# PHOTODIODE.net
KiCad netlist of a schematic drawn in Altium Designer
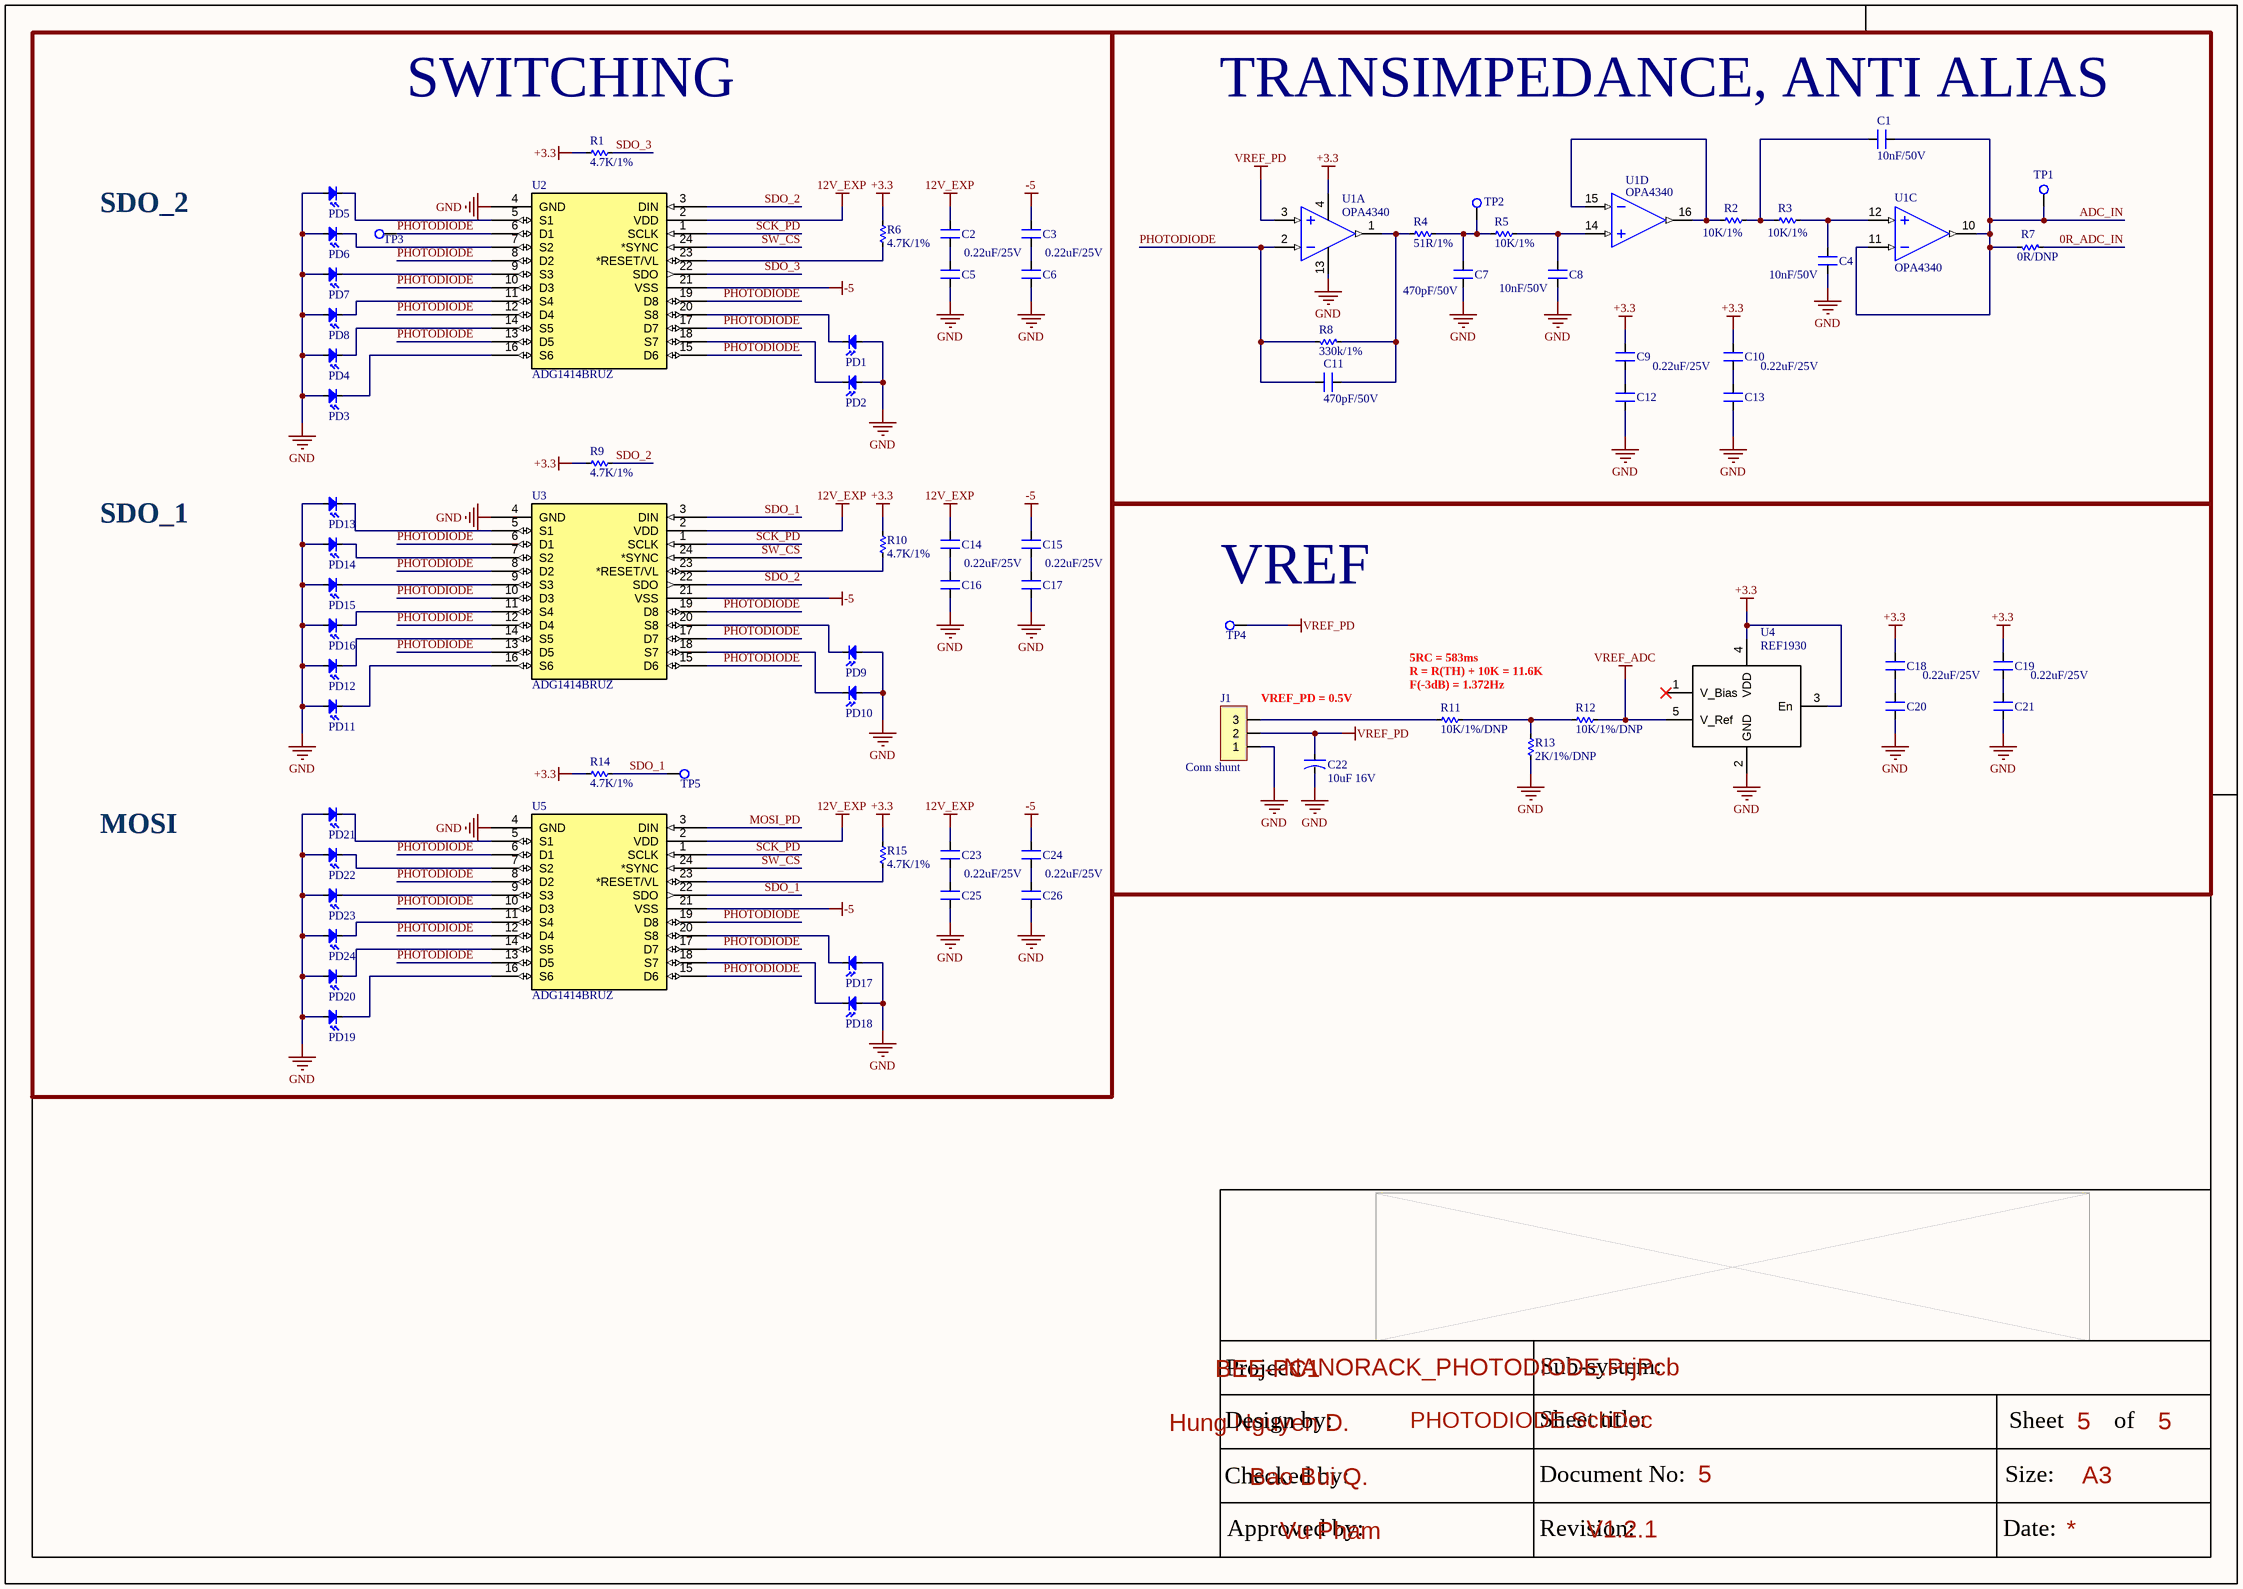
[diagram p0: PHOTODIODE.SchDoc]

(export (version "E")
  (design (tool "Eeschema 10.0.6"))
  (components
    (comp (ref "C1")
      (value "10nF/50V")
      (footprint "CN-SMD-0603")
      (description "CL10B103KB8NNNC")
      (libsource (lib "Capacitors") (part "CM"))
    )
    (comp (ref "C2")
      (value "0.22uF/25V")
      (footprint "CN-SMD-0603")
      (description "CL10B224KA8NNNC")
      (libsource (lib "Capacitors") (part "CM"))
    )
    (comp (ref "C3")
      (value "0.22uF/25V")
      (footprint "CN-SMD-0603")
      (description "CL10B224KA8NNNC")
      (libsource (lib "Capacitors") (part "CM"))
    )
    (comp (ref "C4")
      (value "10nF/50V")
      (footprint "CN-SMD-0603")
      (description "CL10B103KB8NNNC")
      (libsource (lib "Capacitors") (part "CM"))
    )
    (comp (ref "C5")
      (value "0.22uF/25V")
      (footprint "CN-SMD-0603")
      (description "CL10B224KA8NNNC")
      (libsource (lib "Capacitors") (part "CM"))
    )
    (comp (ref "C6")
      (value "0.22uF/25V")
      (footprint "CN-SMD-0603")
      (description "CL10B224KA8NNNC")
      (libsource (lib "Capacitors") (part "CM"))
    )
    (comp (ref "C7")
      (value "470pF/50V")
      (footprint "CN-SMD-0603")
      (description "CL10B471KB8NNNC")
      (libsource (lib "Capacitors") (part "CM"))
    )
    (comp (ref "C8")
      (value "10nF/50V")
      (footprint "CN-SMD-0603")
      (description "CL10B103KB8NNNC")
      (libsource (lib "Capacitors") (part "CM"))
    )
    (comp (ref "C9")
      (value "0.22uF/25V")
      (footprint "CN-SMD-0603")
      (description "CL10B224KA8NNNC")
      (libsource (lib "Capacitors") (part "CM"))
    )
    (comp (ref "C10")
      (value "0.22uF/25V")
      (footprint "CN-SMD-0603")
      (description "CL10B224KA8NNNC")
      (libsource (lib "Capacitors") (part "CM"))
    )
    (comp (ref "C11")
      (value "470pF/50V")
      (footprint "CN-SMD-0603")
      (description "CL10B471KB8NNNC")
      (libsource (lib "Capacitors") (part "CM"))
    )
    (comp (ref "C12")
      (value "0.22uF/25V")
      (footprint "CN-SMD-0603")
      (description "CL10B224KA8NNNC")
      (libsource (lib "Capacitors") (part "CM"))
    )
    (comp (ref "C13")
      (value "0.22uF/25V")
      (footprint "CN-SMD-0603")
      (description "CL10B224KA8NNNC")
      (libsource (lib "Capacitors") (part "CM"))
    )
    (comp (ref "C14")
      (value "0.22uF/25V")
      (footprint "CN-SMD-0603")
      (description "CL10B224KA8NNNC")
      (libsource (lib "Capacitors") (part "CM"))
    )
    (comp (ref "C15")
      (value "0.22uF/25V")
      (footprint "CN-SMD-0603")
      (description "CL10B224KA8NNNC")
      (libsource (lib "Capacitors") (part "CM"))
    )
    (comp (ref "C16")
      (value "0.22uF/25V")
      (footprint "CN-SMD-0603")
      (description "CL10B224KA8NNNC")
      (libsource (lib "Capacitors") (part "CM"))
    )
    (comp (ref "C17")
      (value "0.22uF/25V")
      (footprint "CN-SMD-0603")
      (description "CL10B224KA8NNNC")
      (libsource (lib "Capacitors") (part "CM"))
    )
    (comp (ref "C18")
      (value "0.22uF/25V")
      (footprint "CN-SMD-0603")
      (description "CL10B224KA8NNNC")
      (libsource (lib "Capacitors") (part "CM"))
    )
    (comp (ref "C19")
      (value "0.22uF/25V")
      (footprint "CN-SMD-0603")
      (description "CL10B224KA8NNNC")
      (libsource (lib "Capacitors") (part "CM"))
    )
    (comp (ref "C20")
      (value "0.22uF/25V")
      (footprint "CN-SMD-0603")
      (description "CL10B224KA8NNNC")
      (libsource (lib "Capacitors") (part "CM"))
    )
    (comp (ref "C21")
      (value "0.22uF/25V")
      (footprint "CN-SMD-0603")
      (description "CL10B224KA8NNNC")
      (libsource (lib "Capacitors") (part "CM"))
    )
    (comp (ref "C22")
      (value "10uF 16V")
      (footprint "CAP_TANT_1206")
      (description "TAJA106K016RNJ")
      (fields (field (name "PUBLISHER") "Altium Limited"))
      (libsource (lib "Library_HUNG") (part "CN-ALU-SMD"))
    )
    (comp (ref "C23")
      (value "0.22uF/25V")
      (footprint "CN-SMD-0603")
      (description "CL10B224KA8NNNC")
      (libsource (lib "Capacitors") (part "CM"))
    )
    (comp (ref "C24")
      (value "0.22uF/25V")
      (footprint "CN-SMD-0603")
      (description "CL10B224KA8NNNC")
      (libsource (lib "Capacitors") (part "CM"))
    )
    (comp (ref "C25")
      (value "0.22uF/25V")
      (footprint "CN-SMD-0603")
      (description "CL10B224KA8NNNC")
      (libsource (lib "Capacitors") (part "CM"))
    )
    (comp (ref "C26")
      (value "0.22uF/25V")
      (footprint "CN-SMD-0603")
      (description "CL10B224KA8NNNC")
      (libsource (lib "Capacitors") (part "CM"))
    )
    (comp (ref "J1")
      (value "Conn shunt")
      (footprint "M50-3930342")
      (description "WR-PHD 2.54 mm Angled Socket Header")
      (fields
        (field (name "MANUFACTURER") "Würth Elektronik eiSos GmbH")
        (field (name "PARTNO") "613003143121")
        (field (name "CREATED BY") "Karrer Zheng")
      )
      (libsource (lib "Library") (part "JP3"))
    )
    (comp (ref "PD1")
      (value "Photodiode")
      (footprint "VEMD5080X01")
      (description "VEMD5080X01")
      (libsource (lib "Library_HUNG") (part "Photodiode"))
    )
    (comp (ref "PD2")
      (value "Photodiode")
      (footprint "VEMD5080X01")
      (description "VEMD5080X01")
      (libsource (lib "Library_HUNG") (part "Photodiode"))
    )
    (comp (ref "PD3")
      (value "Photodiode")
      (footprint "VEMD5080X01")
      (description "VEMD5080X01")
      (libsource (lib "Library_HUNG") (part "Photodiode"))
    )
    (comp (ref "PD4")
      (value "Photodiode")
      (footprint "VEMD5080X01")
      (description "VEMD5080X01")
      (libsource (lib "Library_HUNG") (part "Photodiode"))
    )
    (comp (ref "PD5")
      (value "Photodiode")
      (footprint "VEMD5080X01")
      (description "VEMD5080X01")
      (libsource (lib "Library_HUNG") (part "Photodiode"))
    )
    (comp (ref "PD6")
      (value "Photodiode")
      (footprint "VEMD5080X01")
      (description "VEMD5080X01")
      (libsource (lib "Library_HUNG") (part "Photodiode"))
    )
    (comp (ref "PD7")
      (value "Photodiode")
      (footprint "VEMD5080X01")
      (description "VEMD5080X01")
      (libsource (lib "Library_HUNG") (part "Photodiode"))
    )
    (comp (ref "PD8")
      (value "Photodiode")
      (footprint "VEMD5080X01")
      (description "VEMD5080X01")
      (libsource (lib "Library_HUNG") (part "Photodiode"))
    )
    (comp (ref "PD9")
      (value "Photodiode")
      (footprint "VEMD5080X01")
      (description "VEMD5080X01")
      (libsource (lib "Library_HUNG") (part "Photodiode"))
    )
    (comp (ref "PD10")
      (value "Photodiode")
      (footprint "VEMD5080X01")
      (description "VEMD5080X01")
      (libsource (lib "Library_HUNG") (part "Photodiode"))
    )
    (comp (ref "PD11")
      (value "Photodiode")
      (footprint "VEMD5080X01")
      (description "VEMD5080X01")
      (libsource (lib "Library_HUNG") (part "Photodiode"))
    )
    (comp (ref "PD12")
      (value "Photodiode")
      (footprint "VEMD5080X01")
      (description "VEMD5080X01")
      (libsource (lib "Library_HUNG") (part "Photodiode"))
    )
    (comp (ref "PD13")
      (value "Photodiode")
      (footprint "VEMD5080X01")
      (description "VEMD5080X01")
      (libsource (lib "Library_HUNG") (part "Photodiode"))
    )
    (comp (ref "PD14")
      (value "Photodiode")
      (footprint "VEMD5080X01")
      (description "VEMD5080X01")
      (libsource (lib "Library_HUNG") (part "Photodiode"))
    )
    (comp (ref "PD15")
      (value "Photodiode")
      (footprint "VEMD5080X01")
      (description "VEMD5080X01")
      (libsource (lib "Library_HUNG") (part "Photodiode"))
    )
    (comp (ref "PD16")
      (value "Photodiode")
      (footprint "VEMD5080X01")
      (description "VEMD5080X01")
      (libsource (lib "Library_HUNG") (part "Photodiode"))
    )
    (comp (ref "PD17")
      (value "Photodiode")
      (footprint "VEMD5080X01")
      (description "VEMD5080X01")
      (libsource (lib "Library_HUNG") (part "Photodiode"))
    )
    (comp (ref "PD18")
      (value "Photodiode")
      (footprint "VEMD5080X01")
      (description "VEMD5080X01")
      (libsource (lib "Library_HUNG") (part "Photodiode"))
    )
    (comp (ref "PD19")
      (value "Photodiode")
      (footprint "VEMD5080X01")
      (description "VEMD5080X01")
      (libsource (lib "Library_HUNG") (part "Photodiode"))
    )
    (comp (ref "PD20")
      (value "Photodiode")
      (footprint "VEMD5080X01")
      (description "VEMD5080X01")
      (libsource (lib "Library_HUNG") (part "Photodiode"))
    )
    (comp (ref "PD21")
      (value "Photodiode")
      (footprint "VEMD5080X01")
      (description "VEMD5080X01")
      (libsource (lib "Library_HUNG") (part "Photodiode"))
    )
    (comp (ref "PD22")
      (value "Photodiode")
      (footprint "VEMD5080X01")
      (description "VEMD5080X01")
      (libsource (lib "Library_HUNG") (part "Photodiode"))
    )
    (comp (ref "PD23")
      (value "Photodiode")
      (footprint "VEMD5080X01")
      (description "VEMD5080X01")
      (libsource (lib "Library_HUNG") (part "Photodiode"))
    )
    (comp (ref "PD24")
      (value "Photodiode")
      (footprint "VEMD5080X01")
      (description "VEMD5080X01")
      (libsource (lib "Library_HUNG") (part "Photodiode"))
    )
    (comp (ref "R1")
      (value "4.7K/1%")
      (footprint "RES-SMD-0603")
      (description "ERJ-3EKF4701V")
      (fields
        (field (name "MANUFACTURER") "Generic Components")
        (field (name "PUBLISHER") "Altium Hobart Technology Centre")
      )
      (libsource (lib "Library") (part "Res-SMD"))
    )
    (comp (ref "R2")
      (value "10K/1%")
      (footprint "RES-SMD-0603")
      (description "ERJ-3EKF1002V")
      (fields
        (field (name "MANUFACTURER") "Generic Components")
        (field (name "PUBLISHER") "Altium Hobart Technology Centre")
      )
      (libsource (lib "Library") (part "Res-SMD"))
    )
    (comp (ref "R3")
      (value "10K/1%")
      (footprint "RES-SMD-0603")
      (description "ERJ-3EKF1002V")
      (fields
        (field (name "MANUFACTURER") "Generic Components")
        (field (name "PUBLISHER") "Altium Hobart Technology Centre")
      )
      (libsource (lib "Library") (part "Res-SMD"))
    )
    (comp (ref "R4")
      (value "51R/1%")
      (footprint "RES-SMD-0603")
      (description "ERJ-3EKF51R0V")
      (fields
        (field (name "MANUFACTURER") "Generic Components")
        (field (name "PUBLISHER") "Altium Hobart Technology Centre")
      )
      (libsource (lib "Library") (part "Res-SMD"))
    )
    (comp (ref "R5")
      (value "10K/1%")
      (footprint "RES-SMD-0603")
      (description "ERJ-3EKF1002V")
      (fields
        (field (name "MANUFACTURER") "Generic Components")
        (field (name "PUBLISHER") "Altium Hobart Technology Centre")
      )
      (libsource (lib "Library") (part "Res-SMD"))
    )
    (comp (ref "R6")
      (value "4.7K/1%")
      (footprint "RES-SMD-0603")
      (description "ERJ-3EKF4701V")
      (fields
        (field (name "MANUFACTURER") "Generic Components")
        (field (name "PUBLISHER") "Altium Hobart Technology Centre")
      )
      (libsource (lib "Library") (part "Res-SMD"))
    )
    (comp (ref "R7")
      (value "0R/DNP")
      (footprint "RES-SMD-0603")
      (description "ERJ-3GEY0R00V")
      (fields
        (field (name "MANUFACTURER") "Generic Components")
        (field (name "PUBLISHER") "Altium Hobart Technology Centre")
      )
      (libsource (lib "Library") (part "Res-SMD"))
    )
    (comp (ref "R8")
      (value "330k/1%")
      (footprint "RES-SMD-0603")
      (description "ERJ-3EKF3303V")
      (fields
        (field (name "MANUFACTURER") "Generic Components")
        (field (name "PUBLISHER") "Altium Hobart Technology Centre")
      )
      (libsource (lib "Library") (part "Res-SMD"))
    )
    (comp (ref "R9")
      (value "4.7K/1%")
      (footprint "RES-SMD-0603")
      (description "ERJ-3EKF4701V")
      (fields
        (field (name "MANUFACTURER") "Generic Components")
        (field (name "PUBLISHER") "Altium Hobart Technology Centre")
      )
      (libsource (lib "Library") (part "Res-SMD"))
    )
    (comp (ref "R10")
      (value "4.7K/1%")
      (footprint "RES-SMD-0603")
      (description "ERJ-3EKF4701V")
      (fields
        (field (name "MANUFACTURER") "Generic Components")
        (field (name "PUBLISHER") "Altium Hobart Technology Centre")
      )
      (libsource (lib "Library") (part "Res-SMD"))
    )
    (comp (ref "R11")
      (value "10K/1%/DNP")
      (footprint "RES-SMD-0603")
      (description "ERJ-3EKF1002V")
      (fields
        (field (name "MANUFACTURER") "Generic Components")
        (field (name "PUBLISHER") "Altium Hobart Technology Centre")
      )
      (libsource (lib "Library") (part "Res-SMD"))
    )
    (comp (ref "R12")
      (value "10K/1%/DNP")
      (footprint "RES-SMD-0603")
      (description "ERJ-3EKF1002V")
      (fields
        (field (name "MANUFACTURER") "Generic Components")
        (field (name "PUBLISHER") "Altium Hobart Technology Centre")
      )
      (libsource (lib "Library") (part "Res-SMD"))
    )
    (comp (ref "R13")
      (value "2K/1%/DNP")
      (footprint "RES-SMD-0603")
      (description "ERJ-3EKF2001V")
      (fields
        (field (name "MANUFACTURER") "Generic Components")
        (field (name "PUBLISHER") "Altium Hobart Technology Centre")
      )
      (libsource (lib "Library") (part "Res-SMD"))
    )
    (comp (ref "R14")
      (value "4.7K/1%")
      (footprint "RES-SMD-0603")
      (description "ERJ-3EKF4701V")
      (fields
        (field (name "MANUFACTURER") "Generic Components")
        (field (name "PUBLISHER") "Altium Hobart Technology Centre")
      )
      (libsource (lib "Library") (part "Res-SMD"))
    )
    (comp (ref "R15")
      (value "4.7K/1%")
      (footprint "RES-SMD-0603")
      (description "ERJ-3EKF4701V")
      (fields
        (field (name "MANUFACTURER") "Generic Components")
        (field (name "PUBLISHER") "Altium Hobart Technology Centre")
      )
      (libsource (lib "Library") (part "Res-SMD"))
    )
    (comp (ref "TP1")
      (value "Test_Point")
      (footprint "TESTPOINT")
      (libsource (lib "Library_HUNG") (part "Test_Point"))
    )
    (comp (ref "TP2")
      (value "Test_Point")
      (footprint "TESTPOINT")
      (libsource (lib "Library_HUNG") (part "Test_Point"))
    )
    (comp (ref "TP3")
      (value "Test_Point")
      (footprint "TESTPOINT")
      (libsource (lib "Library_HUNG") (part "Test_Point"))
    )
    (comp (ref "TP4")
      (value "Test_Point")
      (footprint "TESTPOINT")
      (libsource (lib "Library_HUNG") (part "Test_Point"))
    )
    (comp (ref "TP5")
      (value "Test_Point")
      (footprint "TESTPOINT")
      (libsource (lib "Library_HUNG") (part "Test_Point"))
    )
    (comp (ref "U1")
      (value "OPA4340")
      (footprint "SSOP16")
      (description "OPA4340UA/2K5")
      (libsource (lib "Library") (part "OPA4340"))
    )
    (comp (ref "U2")
      (value "ADG1414BRUZ")
      (footprint "TSSOP24")
      (libsource (lib "Library_HUNG") (part "ADG1414BRUZ"))
    )
    (comp (ref "U3")
      (value "ADG1414BRUZ")
      (footprint "TSSOP24")
      (libsource (lib "Library_HUNG") (part "ADG1414BRUZ"))
    )
    (comp (ref "U4")
      (value "REF1930")
      (footprint "SOT23-5")
      (description "REF1941AIDDCT")
      (libsource (lib "Library") (part "REF19xx"))
    )
    (comp (ref "U5")
      (value "ADG1414BRUZ")
      (footprint "TSSOP24")
      (libsource (lib "Library_HUNG") (part "ADG1414BRUZ"))
    )
  )
  (nets
    (net (code "1") (name "+3.3") (class "Default")
      (node (ref "C10") (pin "2") (pinfunction "2_2") (pintype "passive"))
      (node (ref "C18") (pin "2") (pinfunction "2_2") (pintype "passive"))
      (node (ref "C19") (pin "2") (pinfunction "2_2") (pintype "passive"))
      (node (ref "C9") (pin "2") (pinfunction "2_2") (pintype "passive"))
      (node (ref "R1") (pin "2") (pinfunction "2_2") (pintype "passive"))
      (node (ref "R10") (pin "2") (pinfunction "2_2") (pintype "passive"))
      (node (ref "R14") (pin "2") (pinfunction "2_2") (pintype "passive"))
      (node (ref "R15") (pin "2") (pinfunction "2_2") (pintype "passive"))
      (node (ref "R6") (pin "2") (pinfunction "2_2") (pintype "passive"))
      (node (ref "R9") (pin "2") (pinfunction "2_2") (pintype "passive"))
      (node (ref "U1") (pin "4") (pinfunction "+V_4") (pintype "passive"))
      (node (ref "U4") (pin "3") (pinfunction "En_3") (pintype "passive"))
      (node (ref "U4") (pin "4") (pinfunction "VDD_4") (pintype "passive"))
    )
    (net (code "2") (name "-5") (class "Default")
      (node (ref "C15") (pin "2") (pinfunction "2_2") (pintype "passive"))
      (node (ref "C24") (pin "2") (pinfunction "2_2") (pintype "passive"))
      (node (ref "C3") (pin "2") (pinfunction "2_2") (pintype "passive"))
      (node (ref "U2") (pin "21") (pinfunction "VSS_21") (pintype "power_in"))
      (node (ref "U3") (pin "21") (pinfunction "VSS_21") (pintype "power_in"))
      (node (ref "U5") (pin "21") (pinfunction "VSS_21") (pintype "power_in"))
    )
    (net (code "3") (name "/0R_ADC_IN") (class "Default")
      (node (ref "R7") (pin "1") (pinfunction "1_1") (pintype "passive"))
    )
    (net (code "4") (name "/ADC_IN") (class "Default")
      (node (ref "C1") (pin "1") (pinfunction "1_1") (pintype "passive"))
      (node (ref "R7") (pin "2") (pinfunction "2_2") (pintype "passive"))
      (node (ref "TP1") (pin "1") (pintype "power_in"))
      (node (ref "U1") (pin "10") (pinfunction "OUT_10") (pintype "output"))
      (node (ref "U1") (pin "11") (pinfunction "IN-_11") (pintype "input"))
    )
    (net (code "5") (name "/MOSI_PD") (class "Default")
      (node (ref "U5") (pin "3") (pinfunction "DIN_3") (pintype "input"))
    )
    (net (code "6") (name "/PHOTODIODE") (class "Default")
      (node (ref "C11") (pin "1") (pinfunction "1_1") (pintype "passive"))
      (node (ref "R8") (pin "1") (pinfunction "1_1") (pintype "passive"))
      (node (ref "TP3") (pin "1") (pintype "power_in"))
      (node (ref "U1") (pin "2") (pinfunction "IN-_2") (pintype "input"))
      (node (ref "U2") (pin "10") (pinfunction "D3_10") (pintype "bidirectional"))
      (node (ref "U2") (pin "12") (pinfunction "D4_12") (pintype "bidirectional"))
      (node (ref "U2") (pin "13") (pinfunction "D5_13") (pintype "bidirectional"))
      (node (ref "U2") (pin "15") (pinfunction "D6_15") (pintype "bidirectional"))
      (node (ref "U2") (pin "17") (pinfunction "D7_17") (pintype "bidirectional"))
      (node (ref "U2") (pin "19") (pinfunction "D8_19") (pintype "bidirectional"))
      (node (ref "U2") (pin "6") (pinfunction "D1_6") (pintype "bidirectional"))
      (node (ref "U2") (pin "8") (pinfunction "D2_8") (pintype "bidirectional"))
      (node (ref "U3") (pin "10") (pinfunction "D3_10") (pintype "bidirectional"))
      (node (ref "U3") (pin "12") (pinfunction "D4_12") (pintype "bidirectional"))
      (node (ref "U3") (pin "13") (pinfunction "D5_13") (pintype "bidirectional"))
      (node (ref "U3") (pin "15") (pinfunction "D6_15") (pintype "bidirectional"))
      (node (ref "U3") (pin "17") (pinfunction "D7_17") (pintype "bidirectional"))
      (node (ref "U3") (pin "19") (pinfunction "D8_19") (pintype "bidirectional"))
      (node (ref "U3") (pin "6") (pinfunction "D1_6") (pintype "bidirectional"))
      (node (ref "U3") (pin "8") (pinfunction "D2_8") (pintype "bidirectional"))
      (node (ref "U5") (pin "10") (pinfunction "D3_10") (pintype "bidirectional"))
      (node (ref "U5") (pin "12") (pinfunction "D4_12") (pintype "bidirectional"))
      (node (ref "U5") (pin "13") (pinfunction "D5_13") (pintype "bidirectional"))
      (node (ref "U5") (pin "15") (pinfunction "D6_15") (pintype "bidirectional"))
      (node (ref "U5") (pin "17") (pinfunction "D7_17") (pintype "bidirectional"))
      (node (ref "U5") (pin "19") (pinfunction "D8_19") (pintype "bidirectional"))
      (node (ref "U5") (pin "6") (pinfunction "D1_6") (pintype "bidirectional"))
      (node (ref "U5") (pin "8") (pinfunction "D2_8") (pintype "bidirectional"))
    )
    (net (code "7") (name "/SCK_PD") (class "Default")
      (node (ref "U2") (pin "1") (pinfunction "SCLK_1") (pintype "input"))
      (node (ref "U3") (pin "1") (pinfunction "SCLK_1") (pintype "input"))
      (node (ref "U5") (pin "1") (pinfunction "SCLK_1") (pintype "input"))
    )
    (net (code "8") (name "/SDO_1") (class "Default")
      (node (ref "R14") (pin "1") (pinfunction "1_1") (pintype "passive"))
      (node (ref "TP5") (pin "1") (pintype "power_in"))
      (node (ref "U3") (pin "3") (pinfunction "DIN_3") (pintype "input"))
      (node (ref "U5") (pin "22") (pinfunction "SDO_22") (pintype "output"))
    )
    (net (code "9") (name "/SDO_2") (class "Default")
      (node (ref "R9") (pin "1") (pinfunction "1_1") (pintype "passive"))
      (node (ref "U2") (pin "3") (pinfunction "DIN_3") (pintype "input"))
      (node (ref "U3") (pin "22") (pinfunction "SDO_22") (pintype "output"))
    )
    (net (code "10") (name "/SDO_3") (class "Default")
      (node (ref "R1") (pin "1") (pinfunction "1_1") (pintype "passive"))
      (node (ref "U2") (pin "22") (pinfunction "SDO_22") (pintype "output"))
    )
    (net (code "11") (name "/SW_CS") (class "Default")
      (node (ref "U2") (pin "24") (pinfunction "*SYNC_24") (pintype "input"))
      (node (ref "U3") (pin "24") (pinfunction "*SYNC_24") (pintype "input"))
      (node (ref "U5") (pin "24") (pinfunction "*SYNC_24") (pintype "input"))
    )
    (net (code "12") (name "12V_EXP") (class "Default")
      (node (ref "C14") (pin "2") (pinfunction "2_2") (pintype "passive"))
      (node (ref "C2") (pin "2") (pinfunction "2_2") (pintype "passive"))
      (node (ref "C23") (pin "2") (pinfunction "2_2") (pintype "passive"))
      (node (ref "U2") (pin "2") (pinfunction "VDD_2") (pintype "power_in"))
      (node (ref "U3") (pin "2") (pinfunction "VDD_2") (pintype "power_in"))
      (node (ref "U5") (pin "2") (pinfunction "VDD_2") (pintype "power_in"))
    )
    (net (code "13") (name "GND") (class "Default")
      (node (ref "C12") (pin "1") (pinfunction "1_1") (pintype "passive"))
      (node (ref "C13") (pin "1") (pinfunction "1_1") (pintype "passive"))
      (node (ref "C16") (pin "1") (pinfunction "1_1") (pintype "passive"))
      (node (ref "C17") (pin "1") (pinfunction "1_1") (pintype "passive"))
      (node (ref "C20") (pin "1") (pinfunction "1_1") (pintype "passive"))
      (node (ref "C21") (pin "1") (pinfunction "1_1") (pintype "passive"))
      (node (ref "C22") (pin "2") (pinfunction "2_2") (pintype "passive"))
      (node (ref "C25") (pin "1") (pinfunction "1_1") (pintype "passive"))
      (node (ref "C26") (pin "1") (pinfunction "1_1") (pintype "passive"))
      (node (ref "C4") (pin "1") (pinfunction "1_1") (pintype "passive"))
      (node (ref "C5") (pin "1") (pinfunction "1_1") (pintype "passive"))
      (node (ref "C6") (pin "1") (pinfunction "1_1") (pintype "passive"))
      (node (ref "C7") (pin "1") (pinfunction "1_1") (pintype "passive"))
      (node (ref "C8") (pin "1") (pinfunction "1_1") (pintype "passive"))
      (node (ref "J1") (pin "1") (pinfunction "1_1") (pintype "passive"))
      (node (ref "PD1") (pin "1") (pinfunction "A_1") (pintype "passive"))
      (node (ref "PD10") (pin "1") (pinfunction "A_1") (pintype "passive"))
      (node (ref "PD11") (pin "1") (pinfunction "A_1") (pintype "passive"))
      (node (ref "PD12") (pin "1") (pinfunction "A_1") (pintype "passive"))
      (node (ref "PD13") (pin "1") (pinfunction "A_1") (pintype "passive"))
      (node (ref "PD14") (pin "1") (pinfunction "A_1") (pintype "passive"))
      (node (ref "PD15") (pin "1") (pinfunction "A_1") (pintype "passive"))
      (node (ref "PD16") (pin "1") (pinfunction "A_1") (pintype "passive"))
      (node (ref "PD17") (pin "1") (pinfunction "A_1") (pintype "passive"))
      (node (ref "PD18") (pin "1") (pinfunction "A_1") (pintype "passive"))
      (node (ref "PD19") (pin "1") (pinfunction "A_1") (pintype "passive"))
      (node (ref "PD2") (pin "1") (pinfunction "A_1") (pintype "passive"))
      (node (ref "PD20") (pin "1") (pinfunction "A_1") (pintype "passive"))
      (node (ref "PD21") (pin "1") (pinfunction "A_1") (pintype "passive"))
      (node (ref "PD22") (pin "1") (pinfunction "A_1") (pintype "passive"))
      (node (ref "PD23") (pin "1") (pinfunction "A_1") (pintype "passive"))
      (node (ref "PD24") (pin "1") (pinfunction "A_1") (pintype "passive"))
      (node (ref "PD3") (pin "1") (pinfunction "A_1") (pintype "passive"))
      (node (ref "PD4") (pin "1") (pinfunction "A_1") (pintype "passive"))
      (node (ref "PD5") (pin "1") (pinfunction "A_1") (pintype "passive"))
      (node (ref "PD6") (pin "1") (pinfunction "A_1") (pintype "passive"))
      (node (ref "PD7") (pin "1") (pinfunction "A_1") (pintype "passive"))
      (node (ref "PD8") (pin "1") (pinfunction "A_1") (pintype "passive"))
      (node (ref "PD9") (pin "1") (pinfunction "A_1") (pintype "passive"))
      (node (ref "R13") (pin "1") (pinfunction "1_1") (pintype "passive"))
      (node (ref "U1") (pin "13") (pinfunction "-V_13") (pintype "passive"))
      (node (ref "U2") (pin "4") (pinfunction "GND_4") (pintype "power_in"))
      (node (ref "U3") (pin "4") (pinfunction "GND_4") (pintype "power_in"))
      (node (ref "U4") (pin "2") (pinfunction "GND_2") (pintype "passive"))
      (node (ref "U5") (pin "4") (pinfunction "GND_4") (pintype "power_in"))
    )
    (net (code "14") (name "Net-(C1-Pad2)") (class "Default")
      (node (ref "C1") (pin "2") (pinfunction "2_2") (pintype "passive"))
      (node (ref "R2") (pin "2") (pinfunction "2_2") (pintype "passive"))
      (node (ref "R3") (pin "1") (pinfunction "1_1") (pintype "passive"))
    )
    (net (code "15") (name "Net-(C2-Pad1)") (class "Default")
      (node (ref "C2") (pin "1") (pinfunction "1_1") (pintype "passive"))
      (node (ref "C5") (pin "2") (pinfunction "2_2") (pintype "passive"))
    )
    (net (code "16") (name "Net-(C3-Pad1)") (class "Default")
      (node (ref "C3") (pin "1") (pinfunction "1_1") (pintype "passive"))
      (node (ref "C6") (pin "2") (pinfunction "2_2") (pintype "passive"))
    )
    (net (code "17") (name "Net-(C7-Pad2)") (class "Default")
      (node (ref "C7") (pin "2") (pinfunction "2_2") (pintype "passive"))
      (node (ref "R4") (pin "2") (pinfunction "2_2") (pintype "passive"))
      (node (ref "R5") (pin "1") (pinfunction "1_1") (pintype "passive"))
      (node (ref "TP2") (pin "1") (pintype "power_in"))
    )
    (net (code "18") (name "Net-(C10-Pad1)") (class "Default")
      (node (ref "C10") (pin "1") (pinfunction "1_1") (pintype "passive"))
      (node (ref "C13") (pin "2") (pinfunction "2_2") (pintype "passive"))
    )
    (net (code "19") (name "Net-(C12-Pad2)") (class "Default")
      (node (ref "C12") (pin "2") (pinfunction "2_2") (pintype "passive"))
      (node (ref "C9") (pin "1") (pinfunction "1_1") (pintype "passive"))
    )
    (net (code "20") (name "Net-(C14-Pad1)") (class "Default")
      (node (ref "C14") (pin "1") (pinfunction "1_1") (pintype "passive"))
      (node (ref "C16") (pin "2") (pinfunction "2_2") (pintype "passive"))
    )
    (net (code "21") (name "Net-(C15-Pad1)") (class "Default")
      (node (ref "C15") (pin "1") (pinfunction "1_1") (pintype "passive"))
      (node (ref "C17") (pin "2") (pinfunction "2_2") (pintype "passive"))
    )
    (net (code "22") (name "Net-(C18-Pad1)") (class "Default")
      (node (ref "C18") (pin "1") (pinfunction "1_1") (pintype "passive"))
      (node (ref "C20") (pin "2") (pinfunction "2_2") (pintype "passive"))
    )
    (net (code "23") (name "Net-(C19-Pad1)") (class "Default")
      (node (ref "C19") (pin "1") (pinfunction "1_1") (pintype "passive"))
      (node (ref "C21") (pin "2") (pinfunction "2_2") (pintype "passive"))
    )
    (net (code "24") (name "Net-(C23-Pad1)") (class "Default")
      (node (ref "C23") (pin "1") (pinfunction "1_1") (pintype "passive"))
      (node (ref "C25") (pin "2") (pinfunction "2_2") (pintype "passive"))
    )
    (net (code "25") (name "Net-(C24-Pad1)") (class "Default")
      (node (ref "C24") (pin "1") (pinfunction "1_1") (pintype "passive"))
      (node (ref "C26") (pin "2") (pinfunction "2_2") (pintype "passive"))
    )
    (net (code "26") (name "Net-(J1-Pad3)") (class "Default")
      (node (ref "J1") (pin "3") (pinfunction "3_3") (pintype "passive"))
      (node (ref "R11") (pin "1") (pinfunction "1_1") (pintype "passive"))
    )
    (net (code "27") (name "Net-(PD1-K)") (class "Default")
      (node (ref "PD1") (pin "2") (pinfunction "K_2") (pintype "passive"))
      (node (ref "U2") (pin "20") (pinfunction "S8_20") (pintype "bidirectional"))
    )
    (net (code "28") (name "Net-(PD2-K)") (class "Default")
      (node (ref "PD2") (pin "2") (pinfunction "K_2") (pintype "passive"))
      (node (ref "U2") (pin "18") (pinfunction "S7_18") (pintype "bidirectional"))
    )
    (net (code "29") (name "Net-(PD3-K)") (class "Default")
      (node (ref "PD3") (pin "2") (pinfunction "K_2") (pintype "passive"))
      (node (ref "U2") (pin "16") (pinfunction "S6_16") (pintype "bidirectional"))
    )
    (net (code "30") (name "Net-(PD4-K)") (class "Default")
      (node (ref "PD4") (pin "2") (pinfunction "K_2") (pintype "passive"))
      (node (ref "U2") (pin "14") (pinfunction "S5_14") (pintype "bidirectional"))
    )
    (net (code "31") (name "Net-(PD5-K)") (class "Default")
      (node (ref "PD5") (pin "2") (pinfunction "K_2") (pintype "passive"))
      (node (ref "U2") (pin "5") (pinfunction "S1_5") (pintype "bidirectional"))
    )
    (net (code "32") (name "Net-(PD6-K)") (class "Default")
      (node (ref "PD6") (pin "2") (pinfunction "K_2") (pintype "passive"))
      (node (ref "U2") (pin "7") (pinfunction "S2_7") (pintype "bidirectional"))
    )
    (net (code "33") (name "Net-(PD7-K)") (class "Default")
      (node (ref "PD7") (pin "2") (pinfunction "K_2") (pintype "passive"))
      (node (ref "U2") (pin "9") (pinfunction "S3_9") (pintype "bidirectional"))
    )
    (net (code "34") (name "Net-(PD8-K)") (class "Default")
      (node (ref "PD8") (pin "2") (pinfunction "K_2") (pintype "passive"))
      (node (ref "U2") (pin "11") (pinfunction "S4_11") (pintype "bidirectional"))
    )
    (net (code "35") (name "Net-(PD9-K)") (class "Default")
      (node (ref "PD9") (pin "2") (pinfunction "K_2") (pintype "passive"))
      (node (ref "U3") (pin "20") (pinfunction "S8_20") (pintype "bidirectional"))
    )
    (net (code "36") (name "Net-(PD10-K)") (class "Default")
      (node (ref "PD10") (pin "2") (pinfunction "K_2") (pintype "passive"))
      (node (ref "U3") (pin "18") (pinfunction "S7_18") (pintype "bidirectional"))
    )
    (net (code "37") (name "Net-(PD11-K)") (class "Default")
      (node (ref "PD11") (pin "2") (pinfunction "K_2") (pintype "passive"))
      (node (ref "U3") (pin "16") (pinfunction "S6_16") (pintype "bidirectional"))
    )
    (net (code "38") (name "Net-(PD12-K)") (class "Default")
      (node (ref "PD12") (pin "2") (pinfunction "K_2") (pintype "passive"))
      (node (ref "U3") (pin "14") (pinfunction "S5_14") (pintype "bidirectional"))
    )
    (net (code "39") (name "Net-(PD13-K)") (class "Default")
      (node (ref "PD13") (pin "2") (pinfunction "K_2") (pintype "passive"))
      (node (ref "U3") (pin "5") (pinfunction "S1_5") (pintype "bidirectional"))
    )
    (net (code "40") (name "Net-(PD14-K)") (class "Default")
      (node (ref "PD14") (pin "2") (pinfunction "K_2") (pintype "passive"))
      (node (ref "U3") (pin "7") (pinfunction "S2_7") (pintype "bidirectional"))
    )
    (net (code "41") (name "Net-(PD15-K)") (class "Default")
      (node (ref "PD15") (pin "2") (pinfunction "K_2") (pintype "passive"))
      (node (ref "U3") (pin "9") (pinfunction "S3_9") (pintype "bidirectional"))
    )
    (net (code "42") (name "Net-(PD16-K)") (class "Default")
      (node (ref "PD16") (pin "2") (pinfunction "K_2") (pintype "passive"))
      (node (ref "U3") (pin "11") (pinfunction "S4_11") (pintype "bidirectional"))
    )
    (net (code "43") (name "Net-(PD17-K)") (class "Default")
      (node (ref "PD17") (pin "2") (pinfunction "K_2") (pintype "passive"))
      (node (ref "U5") (pin "20") (pinfunction "S8_20") (pintype "bidirectional"))
    )
    (net (code "44") (name "Net-(PD18-K)") (class "Default")
      (node (ref "PD18") (pin "2") (pinfunction "K_2") (pintype "passive"))
      (node (ref "U5") (pin "18") (pinfunction "S7_18") (pintype "bidirectional"))
    )
    (net (code "45") (name "Net-(PD19-K)") (class "Default")
      (node (ref "PD19") (pin "2") (pinfunction "K_2") (pintype "passive"))
      (node (ref "U5") (pin "16") (pinfunction "S6_16") (pintype "bidirectional"))
    )
    (net (code "46") (name "Net-(PD20-K)") (class "Default")
      (node (ref "PD20") (pin "2") (pinfunction "K_2") (pintype "passive"))
      (node (ref "U5") (pin "14") (pinfunction "S5_14") (pintype "bidirectional"))
    )
    (net (code "47") (name "Net-(PD21-K)") (class "Default")
      (node (ref "PD21") (pin "2") (pinfunction "K_2") (pintype "passive"))
      (node (ref "U5") (pin "5") (pinfunction "S1_5") (pintype "bidirectional"))
    )
    (net (code "48") (name "Net-(PD22-K)") (class "Default")
      (node (ref "PD22") (pin "2") (pinfunction "K_2") (pintype "passive"))
      (node (ref "U5") (pin "7") (pinfunction "S2_7") (pintype "bidirectional"))
    )
    (net (code "49") (name "Net-(PD23-K)") (class "Default")
      (node (ref "PD23") (pin "2") (pinfunction "K_2") (pintype "passive"))
      (node (ref "U5") (pin "9") (pinfunction "S3_9") (pintype "bidirectional"))
    )
    (net (code "50") (name "Net-(PD24-K)") (class "Default")
      (node (ref "PD24") (pin "2") (pinfunction "K_2") (pintype "passive"))
      (node (ref "U5") (pin "11") (pinfunction "S4_11") (pintype "bidirectional"))
    )
    (net (code "51") (name "Net-(R11-Pad2)") (class "Default")
      (node (ref "R11") (pin "2") (pinfunction "2_2") (pintype "passive"))
      (node (ref "R12") (pin "2") (pinfunction "2_2") (pintype "passive"))
      (node (ref "R13") (pin "2") (pinfunction "2_2") (pintype "passive"))
    )
    (net (code "52") (name "Net-(U1A-OUT)") (class "Default")
      (node (ref "C11") (pin "2") (pinfunction "2_2") (pintype "passive"))
      (node (ref "R4") (pin "1") (pinfunction "1_1") (pintype "passive"))
      (node (ref "R8") (pin "2") (pinfunction "2_2") (pintype "passive"))
      (node (ref "U1") (pin "1") (pinfunction "OUT_1") (pintype "output"))
    )
    (net (code "53") (name "Net-(U1C-IN+)") (class "Default")
      (node (ref "C4") (pin "2") (pinfunction "2_2") (pintype "passive"))
      (node (ref "R3") (pin "2") (pinfunction "2_2") (pintype "passive"))
      (node (ref "U1") (pin "12") (pinfunction "IN+_12") (pintype "input"))
    )
    (net (code "54") (name "Net-(U1D-IN+)") (class "Default")
      (node (ref "C8") (pin "2") (pinfunction "2_2") (pintype "passive"))
      (node (ref "R5") (pin "2") (pinfunction "2_2") (pintype "passive"))
      (node (ref "U1") (pin "14") (pinfunction "IN+_14") (pintype "input"))
    )
    (net (code "55") (name "Net-(U1D-IN-)") (class "Default")
      (node (ref "R2") (pin "1") (pinfunction "1_1") (pintype "passive"))
      (node (ref "U1") (pin "15") (pinfunction "IN-_15") (pintype "input"))
      (node (ref "U1") (pin "16") (pinfunction "OUT_16") (pintype "output"))
    )
    (net (code "56") (name "Net-(U2-*RESET{slash}VL)") (class "Default")
      (node (ref "R6") (pin "1") (pinfunction "1_1") (pintype "passive"))
      (node (ref "U2") (pin "23") (pinfunction "*RESET/VL_23") (pintype "bidirectional"))
    )
    (net (code "57") (name "Net-(U3-*RESET{slash}VL)") (class "Default")
      (node (ref "R10") (pin "1") (pinfunction "1_1") (pintype "passive"))
      (node (ref "U3") (pin "23") (pinfunction "*RESET/VL_23") (pintype "bidirectional"))
    )
    (net (code "58") (name "Net-(U5-*RESET{slash}VL)") (class "Default")
      (node (ref "R15") (pin "1") (pinfunction "1_1") (pintype "passive"))
      (node (ref "U5") (pin "23") (pinfunction "*RESET/VL_23") (pintype "bidirectional"))
    )
    (net (code "59") (name "VREF_ADC") (class "Default")
      (node (ref "R12") (pin "1") (pinfunction "1_1") (pintype "passive"))
      (node (ref "U4") (pin "5") (pinfunction "V_Ref_5") (pintype "passive"))
    )
    (net (code "60") (name "VREF_PD") (class "Default")
      (node (ref "C22") (pin "1") (pinfunction "1_1") (pintype "passive"))
      (node (ref "J1") (pin "2") (pinfunction "2_2") (pintype "passive"))
      (node (ref "TP4") (pin "1") (pintype "power_in"))
      (node (ref "U1") (pin "3") (pinfunction "IN+_3") (pintype "input"))
    )
    (net (code "61") (name "unconnected-(U4-V_Bias-Pad1)") (class "Default")
      (node (ref "U4") (pin "1") (pinfunction "V_Bias_1") (pintype "passive+no_connect"))
    )
  )
)
